# power.net
KiCad netlist of a schematic drawn in Altium Designer
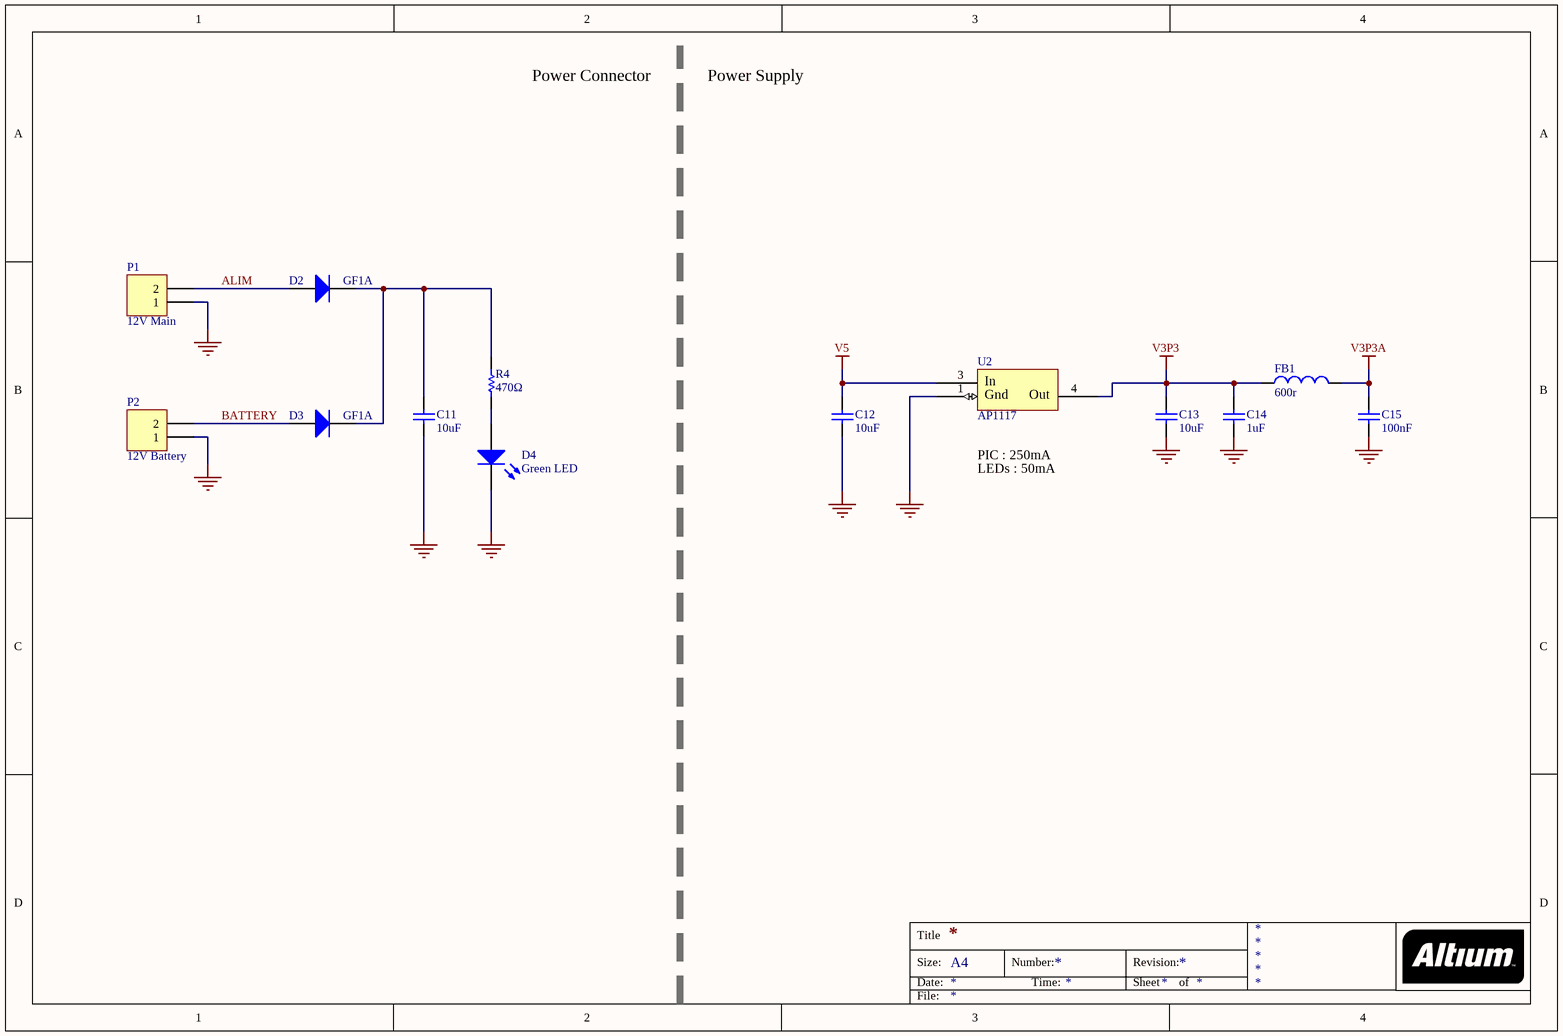
[diagram p0: power.SchDoc]

(export (version "E")
  (design (tool "Eeschema 10.0.6"))
  (components
    (comp (ref "C11")
      (value "10uF")
      (footprint "CAPC2012N")
      (description "Capacitor")
      (fields (field (name "PUBLISHER") "Altium Limited"))
      (libsource (lib "Miscellaneous Devices") (part "Cap"))
    )
    (comp (ref "C12")
      (value "10uF")
      (footprint "CAPC2012N")
      (description "Capacitor")
      (fields (field (name "PUBLISHER") "Altium Limited"))
      (libsource (lib "Miscellaneous Devices") (part "Cap"))
    )
    (comp (ref "C13")
      (value "10uF")
      (footprint "CAPC2012N")
      (description "Capacitor")
      (fields (field (name "PUBLISHER") "Altium Limited"))
      (libsource (lib "Miscellaneous Devices") (part "Cap"))
    )
    (comp (ref "C14")
      (value "1uF")
      (footprint "CAPC1608N")
      (description "Capacitor")
      (fields (field (name "PUBLISHER") "Altium Limited"))
      (libsource (lib "Miscellaneous Devices") (part "Cap"))
    )
    (comp (ref "C15")
      (value "100nF")
      (footprint "CAPC1608N")
      (description "Capacitor")
      (fields (field (name "PUBLISHER") "Altium Limited"))
      (libsource (lib "Miscellaneous Devices") (part "Cap"))
    )
    (comp (ref "D2")
      (value "GF1A")
      (footprint "SMA/DO-214AC_21")
      (description "Default Diode")
      (fields (field (name "PUBLISHER") "Altium Limited"))
      (libsource (lib "Miscellaneous Devices") (part "Diode"))
    )
    (comp (ref "D3")
      (value "GF1A")
      (footprint "SMA/DO-214AC_21")
      (description "Default Diode")
      (fields (field (name "PUBLISHER") "Altium Limited"))
      (libsource (lib "Miscellaneous Devices") (part "Diode"))
    )
    (comp (ref "D4")
      (value "Green LED")
      (footprint "LED 0805")
      (description "Typical INFRARED GaAs LED")
      (fields (field (name "PUBLISHER") "Altium Limited"))
      (libsource (lib "Miscellaneous Devices") (part "LED0"))
    )
    (comp (ref "FB1")
      (value "600r")
      (footprint "INDC1608AN")
      (description "Inductor")
      (fields (field (name "PUBLISHER") "Altium Limited"))
      (libsource (lib "Miscellaneous Devices") (part "Inductor"))
    )
    (comp (ref "P1")
      (value "12V Main")
      (footprint "PHOENIX_1985195")
      (description "Header, 2-Pin")
      (fields (field (name "PUBLISHER") "Altium Limited"))
      (libsource (lib "Miscellaneous Connectors") (part "Header 2"))
    )
    (comp (ref "P2")
      (value "12V Battery")
      (footprint "PHOENIX_1985195")
      (description "Header, 2-Pin")
      (fields (field (name "PUBLISHER") "Altium Limited"))
      (libsource (lib "Miscellaneous Connectors") (part "Header 2"))
    )
    (comp (ref "R4")
      (value "470Ω")
      (footprint "RESC1608N")
      (description "Resistor")
      (fields (field (name "PUBLISHER") "Altium Limited"))
      (libsource (lib "Miscellaneous Devices") (part "Res1"))
    )
    (comp (ref "U2")
      (value "AP1117")
      (footprint "TD03B_N")
      (description "1A LDO, 18V input, DPAK")
      (libsource (lib "TP2lib") (part "AP1117"))
    )
  )
  (nets
    (net (code "1") (name "/ALIM") (class "Default")
      (node (ref "D2") (pin "1") (pinfunction "A_1") (pintype "passive"))
      (node (ref "P1") (pin "2") (pinfunction "2_2") (pintype "passive"))
    )
    (net (code "2") (name "/BATTERY") (class "Default")
      (node (ref "D3") (pin "1") (pinfunction "A_1") (pintype "passive"))
      (node (ref "P2") (pin "2") (pinfunction "2_2") (pintype "passive"))
    )
    (net (code "3") (name "GND") (class "Default")
      (node (ref "C11") (pin "1") (pinfunction "1_1") (pintype "passive"))
      (node (ref "C12") (pin "1") (pinfunction "1_1") (pintype "passive"))
      (node (ref "C13") (pin "1") (pinfunction "1_1") (pintype "passive"))
      (node (ref "C14") (pin "1") (pinfunction "1_1") (pintype "passive"))
      (node (ref "C15") (pin "1") (pinfunction "1_1") (pintype "passive"))
      (node (ref "D4") (pin "2") (pinfunction "K_2") (pintype "passive"))
      (node (ref "P1") (pin "1") (pinfunction "1_1") (pintype "passive"))
      (node (ref "P2") (pin "1") (pinfunction "1_1") (pintype "passive"))
      (node (ref "U2") (pin "1") (pinfunction "1_1") (pintype "bidirectional"))
    )
    (net (code "4") (name "Net-(D2-K)") (class "Default")
      (node (ref "C11") (pin "2") (pinfunction "2_2") (pintype "passive"))
      (node (ref "D2") (pin "2") (pinfunction "K_2") (pintype "passive"))
      (node (ref "D3") (pin "2") (pinfunction "K_2") (pintype "passive"))
      (node (ref "R4") (pin "2") (pinfunction "2_2") (pintype "passive"))
    )
    (net (code "5") (name "Net-(D4-A)") (class "Default")
      (node (ref "D4") (pin "1") (pinfunction "A_1") (pintype "passive"))
      (node (ref "R4") (pin "1") (pinfunction "1_1") (pintype "passive"))
    )
    (net (code "6") (name "V3P3") (class "Default")
      (node (ref "C13") (pin "2") (pinfunction "2_2") (pintype "passive"))
      (node (ref "C14") (pin "2") (pinfunction "2_2") (pintype "passive"))
      (node (ref "FB1") (pin "1") (pinfunction "1_1") (pintype "passive"))
      (node (ref "U2") (pin "4") (pinfunction "4_4") (pintype "power_in"))
    )
    (net (code "7") (name "V3P3A") (class "Default")
      (node (ref "C15") (pin "2") (pinfunction "2_2") (pintype "passive"))
      (node (ref "FB1") (pin "2") (pinfunction "2_2") (pintype "passive"))
    )
    (net (code "8") (name "V5") (class "Default")
      (node (ref "C12") (pin "2") (pinfunction "2_2") (pintype "passive"))
      (node (ref "U2") (pin "3") (pinfunction "3_3") (pintype "power_in"))
    )
  )
)
